# HeadBoard.net
KiCad netlist of a schematic drawn in Altium Designer
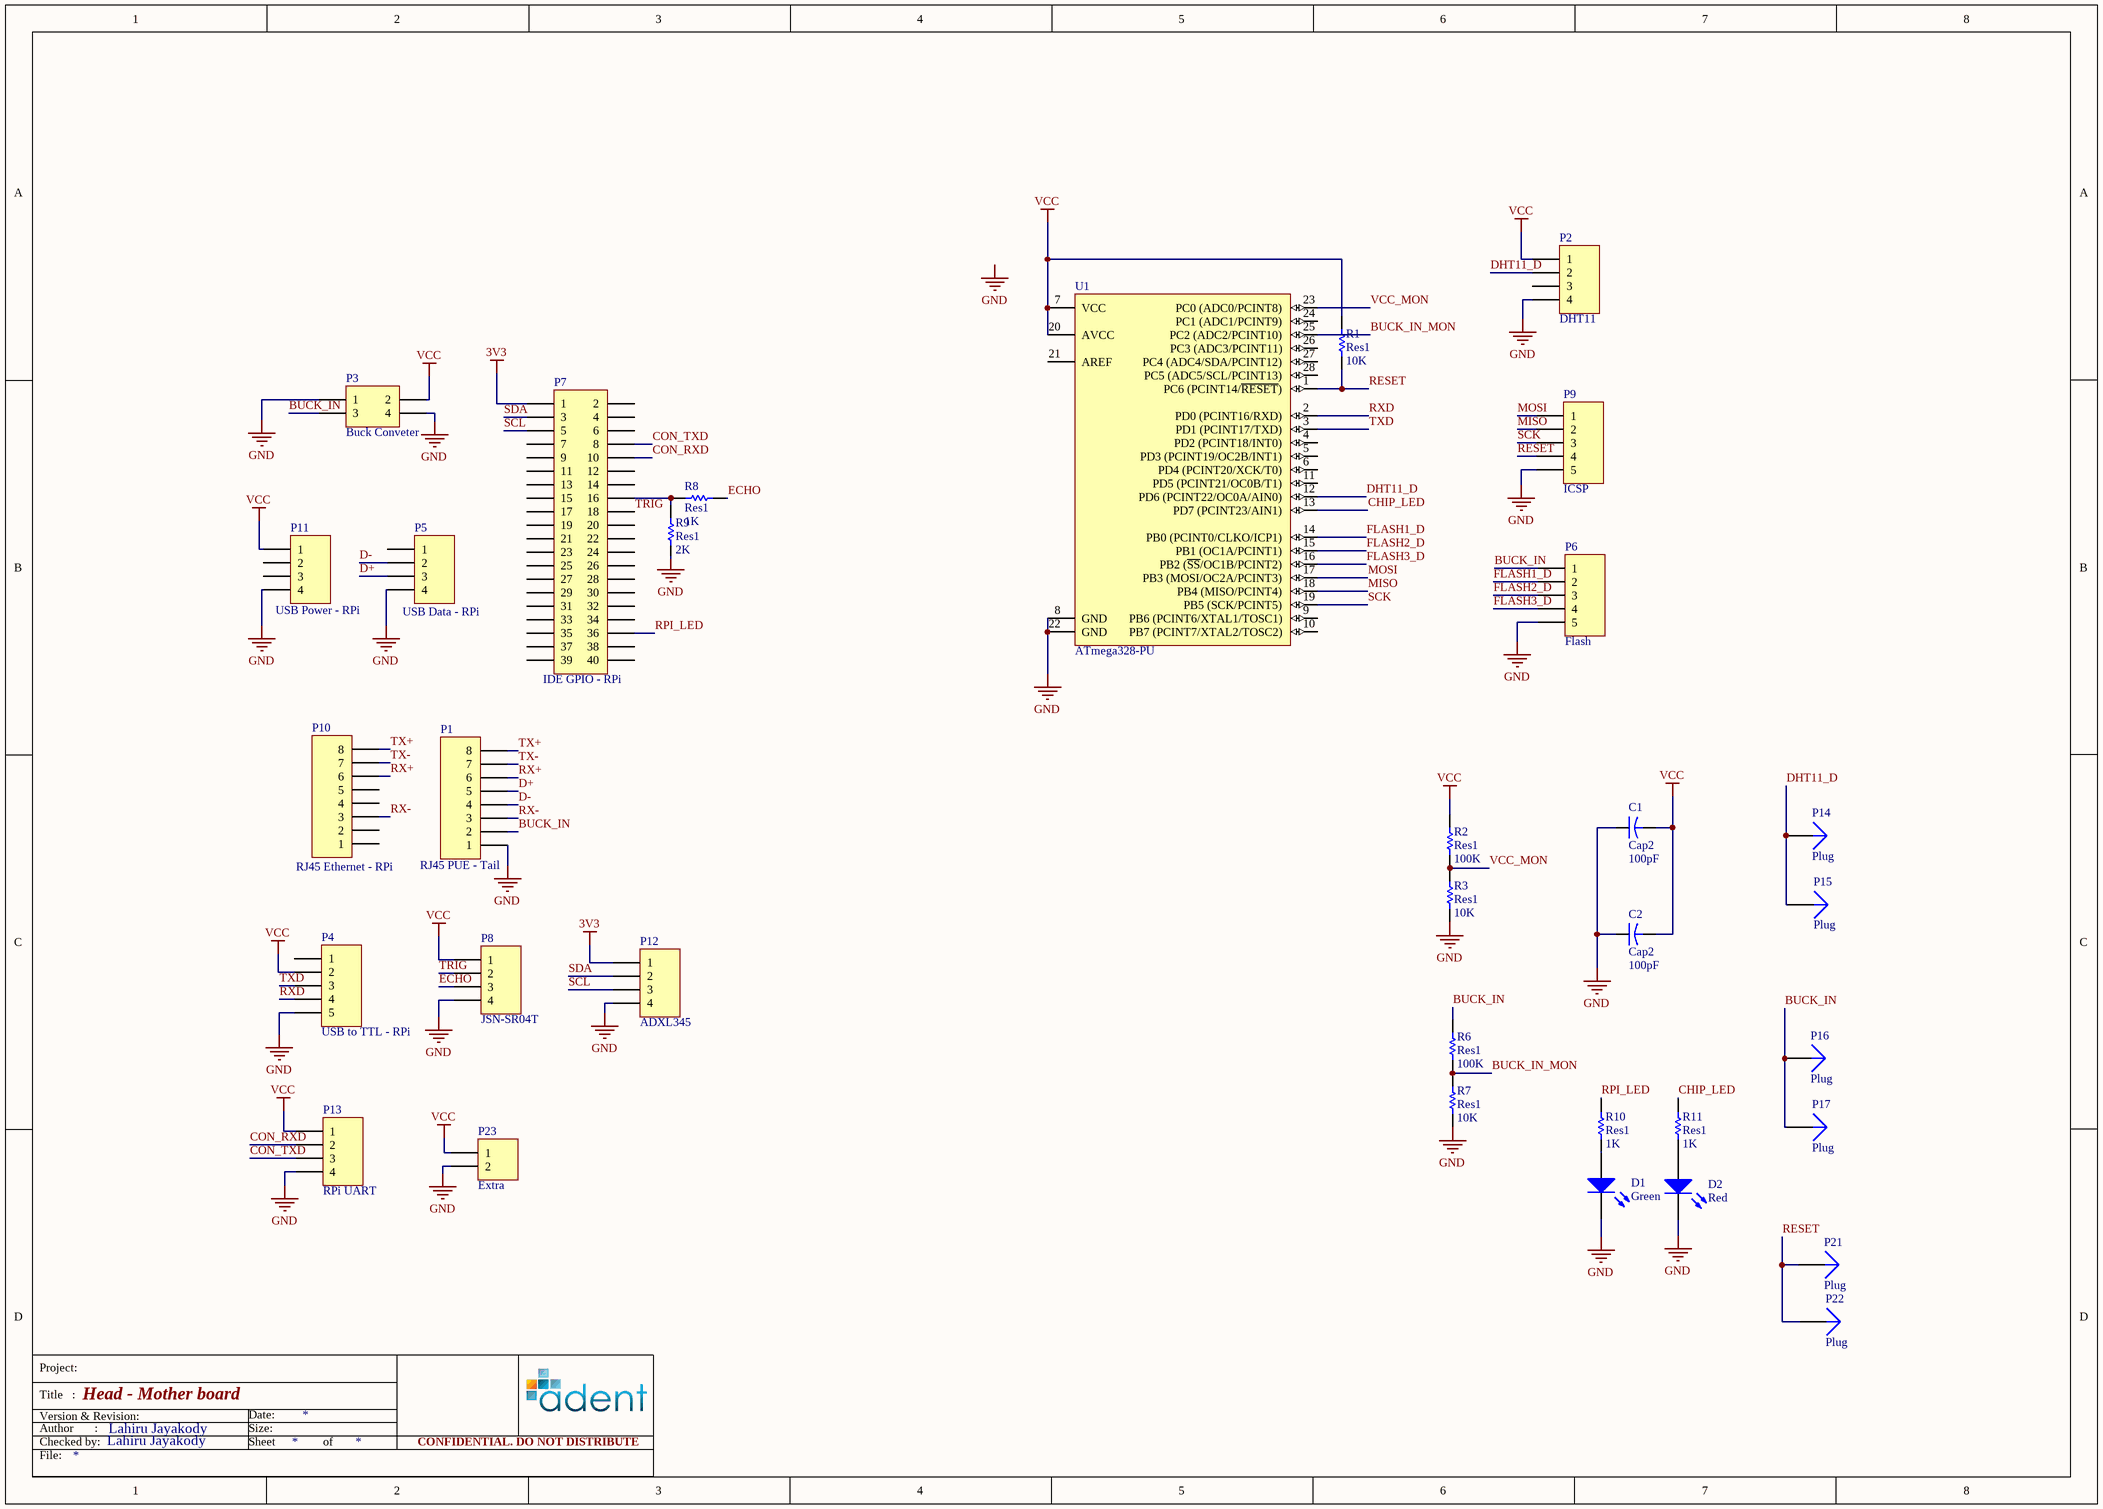
[diagram p0: HeadBoard.SchDoc]

(export (version "E")
  (design (tool "Eeschema 10.0.6"))
  (components
    (comp (ref "C1")
      (value "Cap2")
      (footprint "CAPR5-4X5")
      (description "Capacitor")
      (fields (field (name "ALTIUM_VALUE") "100pF") (field (name "PUBLISHER") "Altium Limited"))
      (libsource (lib "Miscellaneous Devices") (part "Cap2"))
    )
    (comp (ref "C2")
      (value "Cap2")
      (footprint "CAPR5-4X5")
      (description "Capacitor")
      (fields (field (name "ALTIUM_VALUE") "100pF") (field (name "PUBLISHER") "Altium Limited"))
      (libsource (lib "Miscellaneous Devices") (part "Cap2"))
    )
    (comp (ref "D1")
      (value "Green")
      (footprint "LED-1")
      (description "Typical RED GaAs LED")
      (fields (field (name "PUBLISHER") "Altium Limited"))
      (libsource (lib "Miscellaneous Devices") (part "LED1"))
    )
    (comp (ref "D2")
      (value "Red")
      (footprint "LED-1")
      (description "Typical RED GaAs LED")
      (fields (field (name "PUBLISHER") "Altium Limited"))
      (libsource (lib "Miscellaneous Devices") (part "LED1"))
    )
    (comp (ref "P1")
      (value "RJ45 PUE - Tail")
      (footprint "RJ45")
      (description "Header, 8-Pin")
      (fields (field (name "PUBLISHER") "Altium Limited"))
      (libsource (lib "Miscellaneous Connectors") (part "Header 8"))
    )
    (comp (ref "P2")
      (value "DHT11")
      (footprint "HDR1X4")
      (description "Header, 4-Pin")
      (fields (field (name "PUBLISHER") "Altium Limited"))
      (libsource (lib "Miscellaneous Connectors") (part "Header 4"))
    )
    (comp (ref "P3")
      (value "Buck Conveter")
      (footprint "PWR_HEADER")
      (description "Header, 2-Pin, Dual row")
      (fields (field (name "PUBLISHER") "Altium Limited"))
      (libsource (lib "Miscellaneous Connectors") (part "Header 2X2"))
    )
    (comp (ref "P4")
      (value "USB to TTL - RPi")
      (footprint "HDR1X5")
      (description "Header, 5-Pin")
      (fields (field (name "PUBLISHER") "Altium Limited"))
      (libsource (lib "Miscellaneous Connectors") (part "Header 5"))
    )
    (comp (ref "P5")
      (value "USB Data - RPi")
      (footprint "USB_Female")
      (description "Header, 4-Pin")
      (fields (field (name "PUBLISHER") "Altium Limited"))
      (libsource (lib "Miscellaneous Connectors") (part "Header 4"))
    )
    (comp (ref "P6")
      (value "Flash")
      (footprint "HDR1X5")
      (description "Header, 5-Pin")
      (fields (field (name "PUBLISHER") "Altium Limited"))
      (libsource (lib "Miscellaneous Connectors") (part "Header 5"))
    )
    (comp (ref "P7")
      (value "IDE GPIO - RPi")
      (footprint "HDR2X20")
      (description "Header, 20-Pin, Dual row")
      (fields (field (name "PUBLISHER") "Altium Limited"))
      (libsource (lib "Miscellaneous Connectors") (part "Header 20X2"))
    )
    (comp (ref "P8")
      (value "JSN-SR04T")
      (footprint "HDR1X4")
      (description "Header, 4-Pin")
      (fields (field (name "PUBLISHER") "Altium Limited"))
      (libsource (lib "Miscellaneous Connectors") (part "Header 4"))
    )
    (comp (ref "P9")
      (value "ICSP")
      (footprint "HDR1X5")
      (description "Header, 5-Pin")
      (fields (field (name "PUBLISHER") "Altium Limited"))
      (libsource (lib "Miscellaneous Connectors") (part "Header 5"))
    )
    (comp (ref "P10")
      (value "RJ45 Ethernet - RPi")
      (footprint "RJ45")
      (description "Header, 8-Pin")
      (fields (field (name "PUBLISHER") "Altium Limited"))
      (libsource (lib "Miscellaneous Connectors") (part "Header 8"))
    )
    (comp (ref "P11")
      (value "USB Power - RPi")
      (footprint "USB_Female")
      (description "Header, 4-Pin")
      (fields (field (name "PUBLISHER") "Altium Limited"))
      (libsource (lib "Miscellaneous Connectors") (part "Header 4"))
    )
    (comp (ref "P12")
      (value "ADXL345")
      (footprint "HDR1X4")
      (description "Header, 4-Pin")
      (fields (field (name "PUBLISHER") "Altium Limited"))
      (libsource (lib "Miscellaneous Connectors") (part "Header 4"))
    )
    (comp (ref "P13")
      (value "RPi UART")
      (footprint "HDR1X4")
      (description "Header, 4-Pin")
      (fields (field (name "PUBLISHER") "Altium Limited"))
      (libsource (lib "Miscellaneous Connectors") (part "Header 4"))
    )
    (comp (ref "P14")
      (value "Plug")
      (footprint "PIN1")
      (fields (field (name "PUBLISHER") "Altium Limited"))
      (libsource (lib "Miscellaneous Connectors") (part "Plug"))
    )
    (comp (ref "P15")
      (value "Plug")
      (footprint "PIN1")
      (fields (field (name "PUBLISHER") "Altium Limited"))
      (libsource (lib "Miscellaneous Connectors") (part "Plug"))
    )
    (comp (ref "P16")
      (value "Plug")
      (footprint "PIN1")
      (fields (field (name "PUBLISHER") "Altium Limited"))
      (libsource (lib "Miscellaneous Connectors") (part "Plug"))
    )
    (comp (ref "P17")
      (value "Plug")
      (footprint "PIN1")
      (fields (field (name "PUBLISHER") "Altium Limited"))
      (libsource (lib "Miscellaneous Connectors") (part "Plug"))
    )
    (comp (ref "P21")
      (value "Plug")
      (footprint "PIN1")
      (fields (field (name "PUBLISHER") "Altium Limited"))
      (libsource (lib "Miscellaneous Connectors") (part "Plug"))
    )
    (comp (ref "P22")
      (value "Plug")
      (footprint "PIN1")
      (fields (field (name "PUBLISHER") "Altium Limited"))
      (libsource (lib "Miscellaneous Connectors") (part "Plug"))
    )
    (comp (ref "P23")
      (value "Extra")
      (footprint "HDR1X2")
      (description "Header, 2-Pin")
      (fields (field (name "PUBLISHER") "Altium Limited"))
      (libsource (lib "Miscellaneous Connectors") (part "Header 2"))
    )
    (comp (ref "R1")
      (value "Res1")
      (footprint "AXIAL-0.3")
      (description "Resistor")
      (fields (field (name "ALTIUM_VALUE") "10K") (field (name "PUBLISHER") "Altium Limited"))
      (libsource (lib "Miscellaneous Devices") (part "Res1"))
    )
    (comp (ref "R2")
      (value "Res1")
      (footprint "AXIAL-0.3")
      (description "Resistor")
      (fields (field (name "ALTIUM_VALUE") "100K") (field (name "PUBLISHER") "Altium Limited"))
      (libsource (lib "Miscellaneous Devices") (part "Res1"))
    )
    (comp (ref "R3")
      (value "Res1")
      (footprint "AXIAL-0.3")
      (description "Resistor")
      (fields (field (name "ALTIUM_VALUE") "10K") (field (name "PUBLISHER") "Altium Limited"))
      (libsource (lib "Miscellaneous Devices") (part "Res1"))
    )
    (comp (ref "R6")
      (value "Res1")
      (footprint "AXIAL-0.3")
      (description "Resistor")
      (fields (field (name "ALTIUM_VALUE") "100K") (field (name "PUBLISHER") "Altium Limited"))
      (libsource (lib "Miscellaneous Devices") (part "Res1"))
    )
    (comp (ref "R7")
      (value "Res1")
      (footprint "AXIAL-0.3")
      (description "Resistor")
      (fields (field (name "ALTIUM_VALUE") "10K") (field (name "PUBLISHER") "Altium Limited"))
      (libsource (lib "Miscellaneous Devices") (part "Res1"))
    )
    (comp (ref "R8")
      (value "Res1")
      (footprint "AXIAL-0.3")
      (description "Resistor")
      (fields (field (name "ALTIUM_VALUE") "1K") (field (name "PUBLISHER") "Altium Limited"))
      (libsource (lib "Miscellaneous Devices") (part "Res1"))
    )
    (comp (ref "R9")
      (value "Res1")
      (footprint "AXIAL-0.3")
      (description "Resistor")
      (fields (field (name "ALTIUM_VALUE") "2K") (field (name "PUBLISHER") "Altium Limited"))
      (libsource (lib "Miscellaneous Devices") (part "Res1"))
    )
    (comp (ref "R10")
      (value "Res1")
      (footprint "AXIAL-0.3")
      (description "Resistor")
      (fields (field (name "ALTIUM_VALUE") "1K") (field (name "PUBLISHER") "Altium Limited"))
      (libsource (lib "Miscellaneous Devices") (part "Res1"))
    )
    (comp (ref "R11")
      (value "Res1")
      (footprint "AXIAL-0.3")
      (description "Resistor")
      (fields (field (name "ALTIUM_VALUE") "1K") (field (name "PUBLISHER") "Altium Limited"))
      (libsource (lib "Miscellaneous Devices") (part "Res1"))
    )
    (comp (ref "U1")
      (value "ATmega328-PU")
      (footprint "28P3")
      (fields (field (name "PUBLISHER") "Altium Limited"))
      (libsource (lib "Atmel Microcontroller 8-Bit megaAVR") (part "ATmega328-PU"))
    )
  )
  (nets
    (net (code "1") (name "/BUCK_IN") (class "Default")
      (node (ref "P1") (pin "2") (pinfunction "2_2") (pintype "passive"))
      (node (ref "P16") (pin "1") (pinfunction "1_1") (pintype "passive"))
      (node (ref "P17") (pin "1") (pinfunction "1_1") (pintype "passive"))
      (node (ref "P3") (pin "3") (pinfunction "3_3") (pintype "passive"))
      (node (ref "P6") (pin "1") (pinfunction "1_1") (pintype "passive"))
      (node (ref "R6") (pin "2") (pinfunction "2_2") (pintype "passive"))
    )
    (net (code "2") (name "/BUCK_IN_MON") (class "Default")
      (node (ref "R6") (pin "1") (pinfunction "1_1") (pintype "passive"))
      (node (ref "R7") (pin "2") (pinfunction "2_2") (pintype "passive"))
      (node (ref "U1") (pin "25") (pinfunction "PC2_(ADC2/PCINT10)_25") (pintype "bidirectional"))
    )
    (net (code "3") (name "/CHIP_LED") (class "Default")
      (node (ref "R11") (pin "2") (pinfunction "2_2") (pintype "passive"))
      (node (ref "U1") (pin "13") (pinfunction "PD7_(PCINT23/AIN1)_13") (pintype "bidirectional"))
    )
    (net (code "4") (name "/CON_RXD") (class "Default")
      (node (ref "P13") (pin "2") (pinfunction "2_2") (pintype "passive"))
      (node (ref "P7") (pin "10") (pinfunction "10_10") (pintype "passive"))
    )
    (net (code "5") (name "/CON_TXD") (class "Default")
      (node (ref "P13") (pin "3") (pinfunction "3_3") (pintype "passive"))
      (node (ref "P7") (pin "8") (pinfunction "8_8") (pintype "passive"))
    )
    (net (code "6") (name "/D+") (class "Default")
      (node (ref "P1") (pin "5") (pinfunction "5_5") (pintype "passive"))
      (node (ref "P5") (pin "3") (pinfunction "3_3") (pintype "passive"))
    )
    (net (code "7") (name "/D-") (class "Default")
      (node (ref "P1") (pin "4") (pinfunction "4_4") (pintype "passive"))
      (node (ref "P5") (pin "2") (pinfunction "2_2") (pintype "passive"))
    )
    (net (code "8") (name "/DHT11_D") (class "Default")
      (node (ref "P14") (pin "1") (pinfunction "1_1") (pintype "passive"))
      (node (ref "P15") (pin "1") (pinfunction "1_1") (pintype "passive"))
      (node (ref "P2") (pin "2") (pinfunction "2_2") (pintype "passive"))
      (node (ref "U1") (pin "12") (pinfunction "PD6_(PCINT22/OC0A/AIN0)_12") (pintype "bidirectional"))
    )
    (net (code "9") (name "/ECHO") (class "Default")
      (node (ref "P8") (pin "3") (pinfunction "3_3") (pintype "passive"))
      (node (ref "R8") (pin "1") (pinfunction "1_1") (pintype "passive"))
    )
    (net (code "10") (name "/FLASH1_D") (class "Default")
      (node (ref "P6") (pin "2") (pinfunction "2_2") (pintype "passive"))
      (node (ref "U1") (pin "14") (pinfunction "PB0_(PCINT0/CLKO/ICP1)_14") (pintype "bidirectional"))
    )
    (net (code "11") (name "/FLASH2_D") (class "Default")
      (node (ref "P6") (pin "3") (pinfunction "3_3") (pintype "passive"))
      (node (ref "U1") (pin "15") (pinfunction "PB1_(OC1A/PCINT1)_15") (pintype "bidirectional"))
    )
    (net (code "12") (name "/FLASH3_D") (class "Default")
      (node (ref "P6") (pin "4") (pinfunction "4_4") (pintype "passive"))
      (node (ref "U1") (pin "16") (pinfunction "PB2_(~{SS}/OC1B/PCINT2)_16") (pintype "bidirectional"))
    )
    (net (code "13") (name "/MISO") (class "Default")
      (node (ref "P9") (pin "2") (pinfunction "2_2") (pintype "passive"))
      (node (ref "U1") (pin "18") (pinfunction "PB4_(MISO/PCINT4)_18") (pintype "bidirectional"))
    )
    (net (code "14") (name "/MOSI") (class "Default")
      (node (ref "P9") (pin "1") (pinfunction "1_1") (pintype "passive"))
      (node (ref "U1") (pin "17") (pinfunction "PB3_(MOSI/OC2A/PCINT3)_17") (pintype "bidirectional"))
    )
    (net (code "15") (name "/RESET") (class "Default")
      (node (ref "P21") (pin "1") (pinfunction "1_1") (pintype "passive"))
      (node (ref "P22") (pin "1") (pinfunction "1_1") (pintype "passive"))
      (node (ref "P9") (pin "4") (pinfunction "4_4") (pintype "passive"))
      (node (ref "R1") (pin "1") (pinfunction "1_1") (pintype "passive"))
      (node (ref "U1") (pin "1") (pinfunction "PC6_(PCINT14/~{RESET})_1") (pintype "bidirectional"))
    )
    (net (code "16") (name "/RPI_LED") (class "Default")
      (node (ref "P7") (pin "36") (pinfunction "36_36") (pintype "passive"))
      (node (ref "R10") (pin "2") (pinfunction "2_2") (pintype "passive"))
    )
    (net (code "17") (name "/RX+") (class "Default")
      (node (ref "P1") (pin "6") (pinfunction "6_6") (pintype "passive"))
      (node (ref "P10") (pin "6") (pinfunction "6_6") (pintype "passive"))
    )
    (net (code "18") (name "/RX-") (class "Default")
      (node (ref "P1") (pin "3") (pinfunction "3_3") (pintype "passive"))
      (node (ref "P10") (pin "3") (pinfunction "3_3") (pintype "passive"))
    )
    (net (code "19") (name "/RXD") (class "Default")
      (node (ref "P4") (pin "4") (pinfunction "4_4") (pintype "passive"))
      (node (ref "U1") (pin "2") (pinfunction "PD0_(PCINT16/RXD)_2") (pintype "bidirectional"))
    )
    (net (code "20") (name "/SCK") (class "Default")
      (node (ref "P9") (pin "3") (pinfunction "3_3") (pintype "passive"))
      (node (ref "U1") (pin "19") (pinfunction "PB5_(SCK/PCINT5)_19") (pintype "bidirectional"))
    )
    (net (code "21") (name "/SCL") (class "Default")
      (node (ref "P12") (pin "3") (pinfunction "3_3") (pintype "passive"))
      (node (ref "P7") (pin "5") (pinfunction "5_5") (pintype "passive"))
    )
    (net (code "22") (name "/SDA") (class "Default")
      (node (ref "P12") (pin "2") (pinfunction "2_2") (pintype "passive"))
      (node (ref "P7") (pin "3") (pinfunction "3_3") (pintype "passive"))
    )
    (net (code "23") (name "/TRIG") (class "Default")
      (node (ref "P7") (pin "18") (pinfunction "18_18") (pintype "passive"))
      (node (ref "P8") (pin "2") (pinfunction "2_2") (pintype "passive"))
    )
    (net (code "24") (name "/TX+") (class "Default")
      (node (ref "P1") (pin "8") (pinfunction "8_8") (pintype "passive"))
      (node (ref "P10") (pin "8") (pinfunction "8_8") (pintype "passive"))
    )
    (net (code "25") (name "/TX-") (class "Default")
      (node (ref "P1") (pin "7") (pinfunction "7_7") (pintype "passive"))
      (node (ref "P10") (pin "7") (pinfunction "7_7") (pintype "passive"))
    )
    (net (code "26") (name "/TXD") (class "Default")
      (node (ref "P4") (pin "3") (pinfunction "3_3") (pintype "passive"))
      (node (ref "U1") (pin "3") (pinfunction "PD1_(PCINT17/TXD)_3") (pintype "bidirectional"))
    )
    (net (code "27") (name "/VCC_MON") (class "Default")
      (node (ref "R2") (pin "1") (pinfunction "1_1") (pintype "passive"))
      (node (ref "R3") (pin "2") (pinfunction "2_2") (pintype "passive"))
      (node (ref "U1") (pin "23") (pinfunction "PC0_(ADC0/PCINT8)_23") (pintype "bidirectional"))
    )
    (net (code "28") (name "3V3") (class "Default")
      (node (ref "P12") (pin "1") (pinfunction "1_1") (pintype "passive"))
      (node (ref "P7") (pin "1") (pinfunction "1_1") (pintype "passive"))
    )
    (net (code "29") (name "GND") (class "Default")
      (node (ref "C1") (pin "1") (pinfunction "1_1") (pintype "passive"))
      (node (ref "C2") (pin "1") (pinfunction "1_1") (pintype "passive"))
      (node (ref "D1") (pin "2") (pinfunction "K_2") (pintype "passive"))
      (node (ref "D2") (pin "2") (pinfunction "K_2") (pintype "passive"))
      (node (ref "P1") (pin "1") (pinfunction "1_1") (pintype "passive"))
      (node (ref "P11") (pin "4") (pinfunction "4_4") (pintype "passive"))
      (node (ref "P12") (pin "4") (pinfunction "4_4") (pintype "passive"))
      (node (ref "P13") (pin "4") (pinfunction "4_4") (pintype "passive"))
      (node (ref "P2") (pin "4") (pinfunction "4_4") (pintype "passive"))
      (node (ref "P23") (pin "2") (pinfunction "2_2") (pintype "passive"))
      (node (ref "P3") (pin "1") (pinfunction "1_1") (pintype "passive"))
      (node (ref "P3") (pin "4") (pinfunction "4_4") (pintype "passive"))
      (node (ref "P4") (pin "5") (pinfunction "5_5") (pintype "passive"))
      (node (ref "P5") (pin "4") (pinfunction "4_4") (pintype "passive"))
      (node (ref "P6") (pin "5") (pinfunction "5_5") (pintype "passive"))
      (node (ref "P8") (pin "4") (pinfunction "4_4") (pintype "passive"))
      (node (ref "P9") (pin "5") (pinfunction "5_5") (pintype "passive"))
      (node (ref "R3") (pin "1") (pinfunction "1_1") (pintype "passive"))
      (node (ref "R7") (pin "1") (pinfunction "1_1") (pintype "passive"))
      (node (ref "R9") (pin "1") (pinfunction "1_1") (pintype "passive"))
      (node (ref "U1") (pin "22") (pinfunction "GND_22") (pintype "power_in"))
      (node (ref "U1") (pin "8") (pinfunction "GND_8") (pintype "power_in"))
    )
    (net (code "30") (name "Net-(D1-A)") (class "Default")
      (node (ref "D1") (pin "1") (pinfunction "A_1") (pintype "passive"))
      (node (ref "R10") (pin "1") (pinfunction "1_1") (pintype "passive"))
    )
    (net (code "31") (name "Net-(D2-A)") (class "Default")
      (node (ref "D2") (pin "1") (pinfunction "A_1") (pintype "passive"))
      (node (ref "R11") (pin "1") (pinfunction "1_1") (pintype "passive"))
    )
    (net (code "32") (name "Net-(P7-Pad16)") (class "Default")
      (node (ref "P7") (pin "16") (pinfunction "16_16") (pintype "passive"))
      (node (ref "R8") (pin "2") (pinfunction "2_2") (pintype "passive"))
      (node (ref "R9") (pin "2") (pinfunction "2_2") (pintype "passive"))
    )
    (net (code "33") (name "VCC") (class "Default")
      (node (ref "C1") (pin "2") (pinfunction "2_2") (pintype "passive"))
      (node (ref "C2") (pin "2") (pinfunction "2_2") (pintype "passive"))
      (node (ref "P11") (pin "1") (pinfunction "1_1") (pintype "passive"))
      (node (ref "P13") (pin "1") (pinfunction "1_1") (pintype "passive"))
      (node (ref "P2") (pin "1") (pinfunction "1_1") (pintype "passive"))
      (node (ref "P23") (pin "1") (pinfunction "1_1") (pintype "passive"))
      (node (ref "P3") (pin "2") (pinfunction "2_2") (pintype "passive"))
      (node (ref "P4") (pin "2") (pinfunction "2_2") (pintype "passive"))
      (node (ref "P8") (pin "1") (pinfunction "1_1") (pintype "passive"))
      (node (ref "R1") (pin "2") (pinfunction "2_2") (pintype "passive"))
      (node (ref "R2") (pin "2") (pinfunction "2_2") (pintype "passive"))
      (node (ref "U1") (pin "20") (pinfunction "AVCC_20") (pintype "power_in"))
      (node (ref "U1") (pin "7") (pinfunction "VCC_7") (pintype "power_in"))
    )
    (net (code "34") (name "unconnected-(P2-Pad3)") (class "Default")
      (node (ref "P2") (pin "3") (pinfunction "3_3") (pintype "passive"))
    )
    (net (code "35") (name "unconnected-(P4-Pad1)") (class "Default")
      (node (ref "P4") (pin "1") (pinfunction "1_1") (pintype "passive"))
    )
    (net (code "36") (name "unconnected-(P5-Pad1)") (class "Default")
      (node (ref "P5") (pin "1") (pinfunction "1_1") (pintype "passive"))
    )
    (net (code "37") (name "unconnected-(P7-Pad2)") (class "Default")
      (node (ref "P7") (pin "2") (pinfunction "2_2") (pintype "passive"))
    )
    (net (code "38") (name "unconnected-(P7-Pad4)") (class "Default")
      (node (ref "P7") (pin "4") (pinfunction "4_4") (pintype "passive"))
    )
    (net (code "39") (name "unconnected-(P7-Pad6)") (class "Default")
      (node (ref "P7") (pin "6") (pinfunction "6_6") (pintype "passive"))
    )
    (net (code "40") (name "unconnected-(P7-Pad7)") (class "Default")
      (node (ref "P7") (pin "7") (pinfunction "7_7") (pintype "passive"))
    )
    (net (code "41") (name "unconnected-(P7-Pad9)") (class "Default")
      (node (ref "P7") (pin "9") (pinfunction "9_9") (pintype "passive"))
    )
    (net (code "42") (name "unconnected-(P7-Pad11)") (class "Default")
      (node (ref "P7") (pin "11") (pinfunction "11_11") (pintype "passive"))
    )
    (net (code "43") (name "unconnected-(P7-Pad12)") (class "Default")
      (node (ref "P7") (pin "12") (pinfunction "12_12") (pintype "passive"))
    )
    (net (code "44") (name "unconnected-(P7-Pad13)") (class "Default")
      (node (ref "P7") (pin "13") (pinfunction "13_13") (pintype "passive"))
    )
    (net (code "45") (name "unconnected-(P7-Pad14)") (class "Default")
      (node (ref "P7") (pin "14") (pinfunction "14_14") (pintype "passive"))
    )
    (net (code "46") (name "unconnected-(P7-Pad15)") (class "Default")
      (node (ref "P7") (pin "15") (pinfunction "15_15") (pintype "passive"))
    )
    (net (code "47") (name "unconnected-(P7-Pad17)") (class "Default")
      (node (ref "P7") (pin "17") (pinfunction "17_17") (pintype "passive"))
    )
    (net (code "48") (name "unconnected-(P7-Pad19)") (class "Default")
      (node (ref "P7") (pin "19") (pinfunction "19_19") (pintype "passive"))
    )
    (net (code "49") (name "unconnected-(P7-Pad20)") (class "Default")
      (node (ref "P7") (pin "20") (pinfunction "20_20") (pintype "passive"))
    )
    (net (code "50") (name "unconnected-(P7-Pad21)") (class "Default")
      (node (ref "P7") (pin "21") (pinfunction "21_21") (pintype "passive"))
    )
    (net (code "51") (name "unconnected-(P7-Pad22)") (class "Default")
      (node (ref "P7") (pin "22") (pinfunction "22_22") (pintype "passive"))
    )
    (net (code "52") (name "unconnected-(P7-Pad23)") (class "Default")
      (node (ref "P7") (pin "23") (pinfunction "23_23") (pintype "passive"))
    )
    (net (code "53") (name "unconnected-(P7-Pad24)") (class "Default")
      (node (ref "P7") (pin "24") (pinfunction "24_24") (pintype "passive"))
    )
    (net (code "54") (name "unconnected-(P7-Pad25)") (class "Default")
      (node (ref "P7") (pin "25") (pinfunction "25_25") (pintype "passive"))
    )
    (net (code "55") (name "unconnected-(P7-Pad26)") (class "Default")
      (node (ref "P7") (pin "26") (pinfunction "26_26") (pintype "passive"))
    )
    (net (code "56") (name "unconnected-(P7-Pad27)") (class "Default")
      (node (ref "P7") (pin "27") (pinfunction "27_27") (pintype "passive"))
    )
    (net (code "57") (name "unconnected-(P7-Pad28)") (class "Default")
      (node (ref "P7") (pin "28") (pinfunction "28_28") (pintype "passive"))
    )
    (net (code "58") (name "unconnected-(P7-Pad29)") (class "Default")
      (node (ref "P7") (pin "29") (pinfunction "29_29") (pintype "passive"))
    )
    (net (code "59") (name "unconnected-(P7-Pad30)") (class "Default")
      (node (ref "P7") (pin "30") (pinfunction "30_30") (pintype "passive"))
    )
    (net (code "60") (name "unconnected-(P7-Pad31)") (class "Default")
      (node (ref "P7") (pin "31") (pinfunction "31_31") (pintype "passive"))
    )
    (net (code "61") (name "unconnected-(P7-Pad32)") (class "Default")
      (node (ref "P7") (pin "32") (pinfunction "32_32") (pintype "passive"))
    )
    (net (code "62") (name "unconnected-(P7-Pad33)") (class "Default")
      (node (ref "P7") (pin "33") (pinfunction "33_33") (pintype "passive"))
    )
    (net (code "63") (name "unconnected-(P7-Pad34)") (class "Default")
      (node (ref "P7") (pin "34") (pinfunction "34_34") (pintype "passive"))
    )
    (net (code "64") (name "unconnected-(P7-Pad35)") (class "Default")
      (node (ref "P7") (pin "35") (pinfunction "35_35") (pintype "passive"))
    )
    (net (code "65") (name "unconnected-(P7-Pad37)") (class "Default")
      (node (ref "P7") (pin "37") (pinfunction "37_37") (pintype "passive"))
    )
    (net (code "66") (name "unconnected-(P7-Pad38)") (class "Default")
      (node (ref "P7") (pin "38") (pinfunction "38_38") (pintype "passive"))
    )
    (net (code "67") (name "unconnected-(P7-Pad39)") (class "Default")
      (node (ref "P7") (pin "39") (pinfunction "39_39") (pintype "passive"))
    )
    (net (code "68") (name "unconnected-(P7-Pad40)") (class "Default")
      (node (ref "P7") (pin "40") (pinfunction "40_40") (pintype "passive"))
    )
    (net (code "69") (name "unconnected-(P10-Pad1)") (class "Default")
      (node (ref "P10") (pin "1") (pinfunction "1_1") (pintype "passive"))
    )
    (net (code "70") (name "unconnected-(P10-Pad2)") (class "Default")
      (node (ref "P10") (pin "2") (pinfunction "2_2") (pintype "passive"))
    )
    (net (code "71") (name "unconnected-(P10-Pad4)") (class "Default")
      (node (ref "P10") (pin "4") (pinfunction "4_4") (pintype "passive"))
    )
    (net (code "72") (name "unconnected-(P10-Pad5)") (class "Default")
      (node (ref "P10") (pin "5") (pinfunction "5_5") (pintype "passive"))
    )
    (net (code "73") (name "unconnected-(P11-Pad2)") (class "Default")
      (node (ref "P11") (pin "2") (pinfunction "2_2") (pintype "passive"))
    )
    (net (code "74") (name "unconnected-(P11-Pad3)") (class "Default")
      (node (ref "P11") (pin "3") (pinfunction "3_3") (pintype "passive"))
    )
    (net (code "75") (name "unconnected-(U1-AREF-Pad21)") (class "Default")
      (node (ref "U1") (pin "21") (pinfunction "AREF_21") (pintype "power_in"))
    )
    (net (code "76") (name "unconnected-(U1-PB6_(PCINT6{slash}XTAL1{slash}TOSC1)-Pad9)") (class "Default")
      (node (ref "U1") (pin "9") (pinfunction "PB6_(PCINT6/XTAL1/TOSC1)_9") (pintype "bidirectional"))
    )
    (net (code "77") (name "unconnected-(U1-PB7_(PCINT7{slash}XTAL2{slash}TOSC2)-Pad10)") (class "Default")
      (node (ref "U1") (pin "10") (pinfunction "PB7_(PCINT7/XTAL2/TOSC2)_10") (pintype "bidirectional"))
    )
    (net (code "78") (name "unconnected-(U1-PC1_(ADC1{slash}PCINT9)-Pad24)") (class "Default")
      (node (ref "U1") (pin "24") (pinfunction "PC1_(ADC1/PCINT9)_24") (pintype "bidirectional"))
    )
    (net (code "79") (name "unconnected-(U1-PC3_(ADC3{slash}PCINT11)-Pad26)") (class "Default")
      (node (ref "U1") (pin "26") (pinfunction "PC3_(ADC3/PCINT11)_26") (pintype "bidirectional"))
    )
    (net (code "80") (name "unconnected-(U1-PC4_(ADC4{slash}SDA{slash}PCINT12)-Pad27)") (class "Default")
      (node (ref "U1") (pin "27") (pinfunction "PC4_(ADC4/SDA/PCINT12)_27") (pintype "bidirectional"))
    )
    (net (code "81") (name "unconnected-(U1-PC5_(ADC5{slash}SCL{slash}PCINT13)-Pad28)") (class "Default")
      (node (ref "U1") (pin "28") (pinfunction "PC5_(ADC5/SCL/PCINT13)_28") (pintype "bidirectional"))
    )
    (net (code "82") (name "unconnected-(U1-PD2_(PCINT18{slash}INT0)-Pad4)") (class "Default")
      (node (ref "U1") (pin "4") (pinfunction "PD2_(PCINT18/INT0)_4") (pintype "bidirectional"))
    )
    (net (code "83") (name "unconnected-(U1-PD3_(PCINT19{slash}OC2B{slash}INT1)-Pad5)") (class "Default")
      (node (ref "U1") (pin "5") (pinfunction "PD3_(PCINT19/OC2B/INT1)_5") (pintype "bidirectional"))
    )
    (net (code "84") (name "unconnected-(U1-PD4_(PCINT20{slash}XCK{slash}T0)-Pad6)") (class "Default")
      (node (ref "U1") (pin "6") (pinfunction "PD4_(PCINT20/XCK/T0)_6") (pintype "bidirectional"))
    )
    (net (code "85") (name "unconnected-(U1-PD5_(PCINT21{slash}OC0B{slash}T1)-Pad11)") (class "Default")
      (node (ref "U1") (pin "11") (pinfunction "PD5_(PCINT21/OC0B/T1)_11") (pintype "bidirectional"))
    )
  )
)
